# Nano_Leonardo_no_3V3.net
KiCad netlist of a schematic drawn in EAGLE
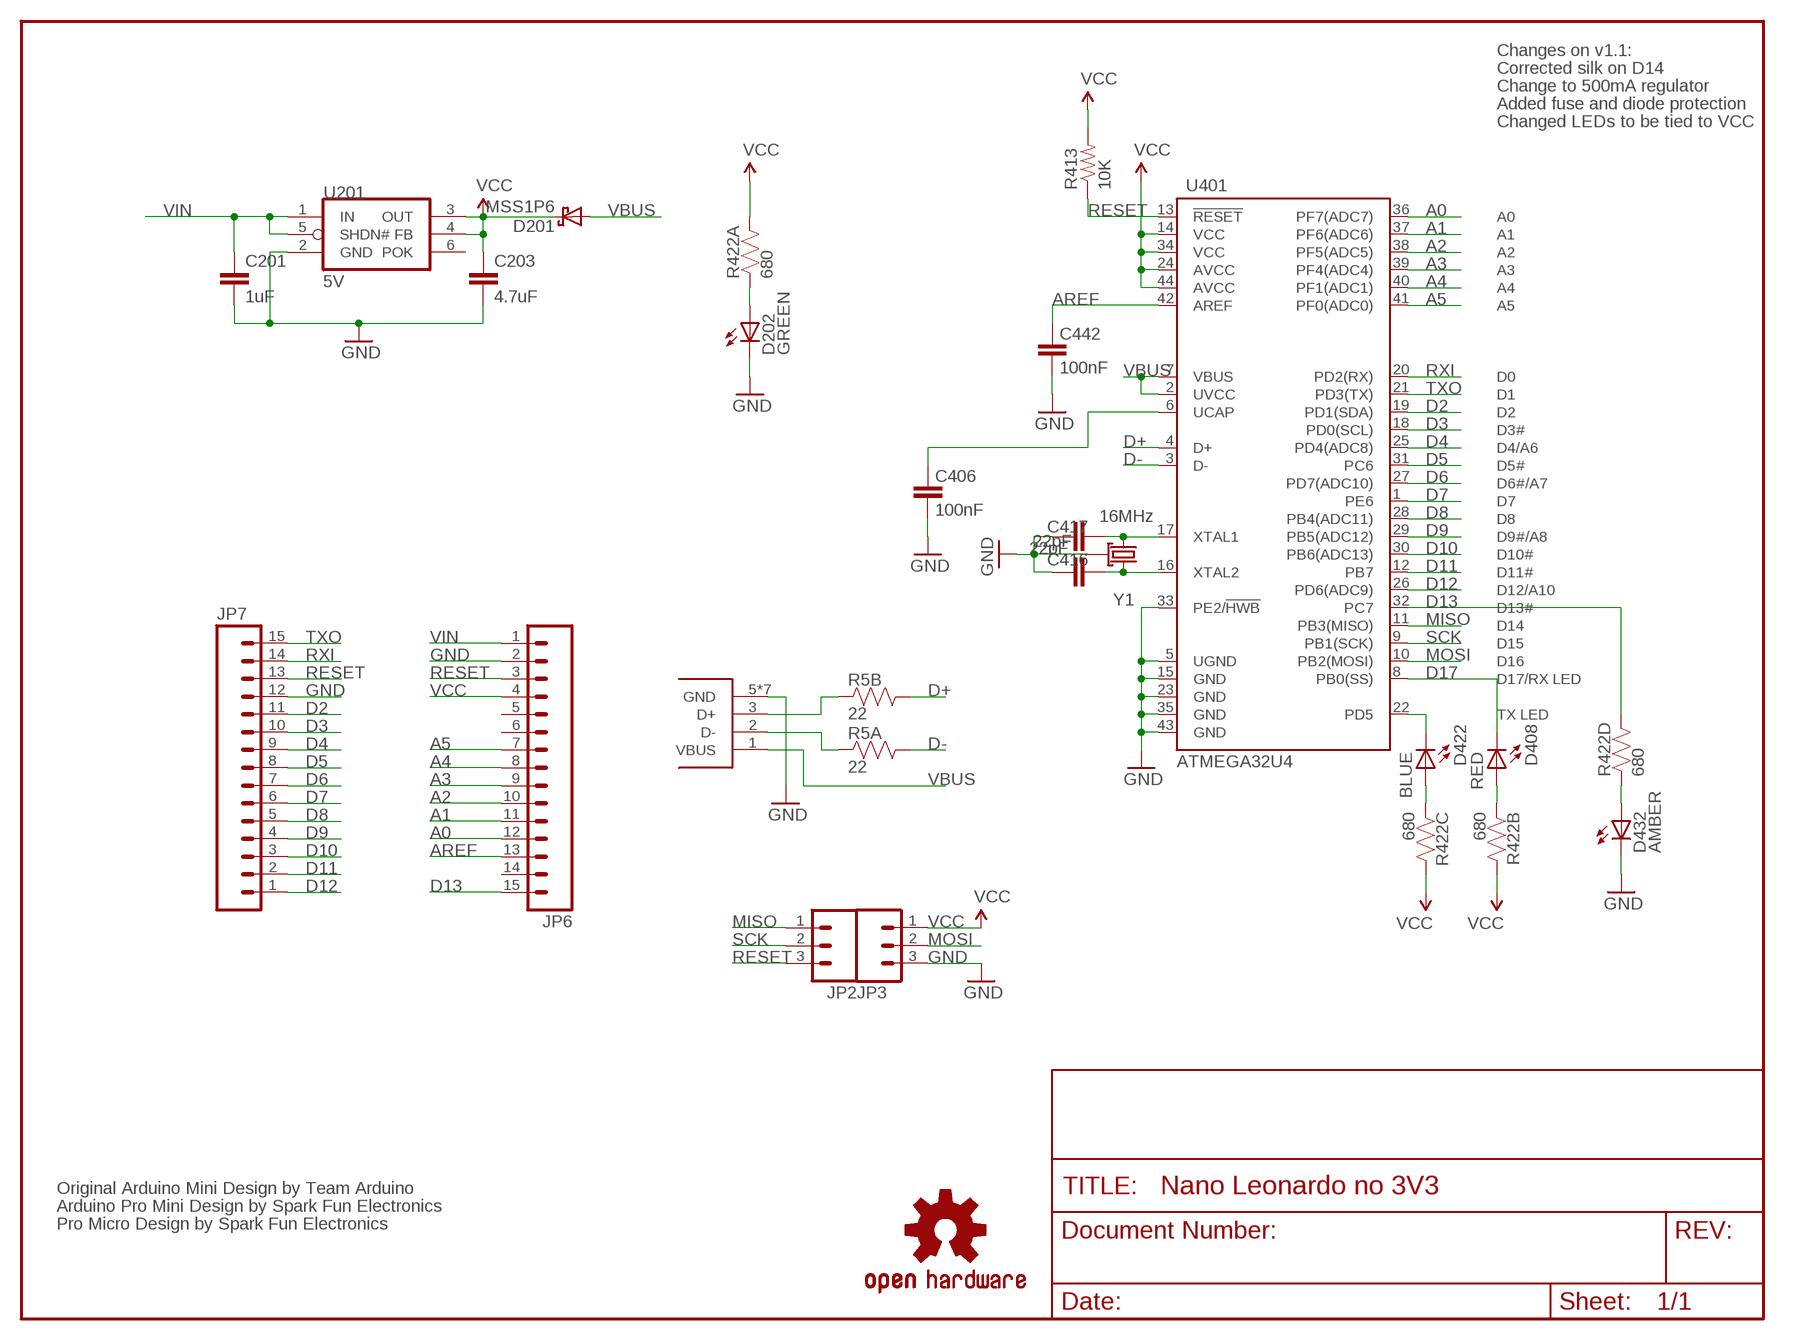
[diagram p0: schematic, sheet 1]

(export (version "E")
  (design (tool "Eeschema 10.0.6"))
  (components
    (comp (ref "C201")
      (value "1uF")
      (footprint "eagle-import:0402-CAP")
      (libsource (lib "eagle-import") (part "CAP0402-CAP"))
    )
    (comp (ref "C203")
      (value "4.7uF")
      (footprint "eagle-import:0402-CAP")
      (libsource (lib "eagle-import") (part "CAP0402-CAP"))
    )
    (comp (ref "C406")
      (value "100nF")
      (footprint "eagle-import:0402-CAP")
      (libsource (lib "eagle-import") (part "CAP0402-CAP"))
    )
    (comp (ref "C416")
      (value "22pF")
      (footprint "eagle-import:0402-CAP")
      (libsource (lib "eagle-import") (part "CAP0402-CAP"))
    )
    (comp (ref "C417")
      (value "22pF")
      (footprint "eagle-import:0402-CAP")
      (libsource (lib "eagle-import") (part "CAP0402-CAP"))
    )
    (comp (ref "C442")
      (value "100nF")
      (footprint "eagle-import:0402-CAP")
      (libsource (lib "eagle-import") (part "CAP0402-CAP"))
    )
    (comp (ref "D201")
      (value "MSS1P6")
      (footprint "eagle-import:MICROSMP")
      (libsource (lib "eagle-import") (part "MSS1P6"))
    )
    (comp (ref "D202")
      (value "GREEN")
      (footprint "eagle-import:LED-0603")
      (libsource (lib "eagle-import") (part "LED0603"))
    )
    (comp (ref "D408")
      (value "RED")
      (footprint "eagle-import:LED-0603")
      (libsource (lib "eagle-import") (part "LED0603"))
    )
    (comp (ref "D422")
      (value "BLUE")
      (footprint "eagle-import:LED-0603")
      (libsource (lib "eagle-import") (part "LED0603"))
    )
    (comp (ref "D432")
      (value "AMBER")
      (footprint "eagle-import:LED-0603")
      (libsource (lib "eagle-import") (part "LED0603"))
    )
    (comp (ref "JP2")
      (value "M031X03_NO_SILK")
      (footprint "eagle-import:1X03_NO_SILK")
      (libsource (lib "eagle-import") (part "M031X03_NO_SILK"))
    )
    (comp (ref "JP3")
      (value "M031X03_NO_SILK")
      (footprint "eagle-import:1X03_NO_SILK")
      (libsource (lib "eagle-import") (part "M031X03_NO_SILK"))
    )
    (comp (ref "JP6")
      (value "M15")
      (footprint "eagle-import:1X15")
      (libsource (lib "eagle-import") (part "M15"))
    )
    (comp (ref "JP7")
      (value "M15")
      (footprint "eagle-import:1X15")
      (libsource (lib "eagle-import") (part "M15"))
    )
    (comp (ref "R5")
      (value "22")
      (footprint "eagle-import:CRA02")
      (libsource (lib "eagle-import") (part "RP2EXB24V"))
    )
    (comp (ref "R413")
      (value "10K")
      (footprint "eagle-import:0402-RES")
      (libsource (lib "eagle-import") (part "RESISTOR0402-RES"))
    )
    (comp (ref "R422")
      (value "680")
      (footprint "eagle-import:CRA04")
      (libsource (lib "eagle-import") (part "RP404"))
    )
    (comp (ref "U$3")
      (value "OSHW-LOGOS")
      (footprint "eagle-import:OSHW-LOGO-S")
      (libsource (lib "eagle-import") (part "OSHW-LOGOS"))
    )
    (comp (ref "U201")
      (value "5V")
      (footprint "eagle-import:SOT-23-6")
      (libsource (lib "eagle-import") (part "MAX8881"))
    )
    (comp (ref "U401")
      (value "ATMEGA32U4")
      (footprint "eagle-import:QFN-44-NOPAD")
      (libsource (lib "eagle-import") (part "ATMEGA32U4QFN2"))
    )
    (comp (ref "X1")
      (value "USB_MICROB_JSTGCT")
      (footprint "eagle-import:USB_MICROB_3075")
      (libsource (lib "eagle-import") (part "USB_MICROB_JSTGCT"))
    )
    (comp (ref "Y1")
      (value "16MHz")
      (footprint "eagle-import:CRYSTAL_SMD_2MM_2_5MM")
      (libsource (lib "eagle-import") (part "CX2520"))
    )
  )
  (nets
    (net (code "1") (name "/A0") (class "Default")
      (node (ref "JP6") (pin "12") (pinfunction "12_12") (pintype "passive"))
      (node (ref "U401") (pin "36") (pinfunction "PF7(ADC7)_36") (pintype "bidirectional"))
    )
    (net (code "2") (name "/A1") (class "Default")
      (node (ref "JP6") (pin "11") (pinfunction "11_11") (pintype "passive"))
      (node (ref "U401") (pin "37") (pinfunction "PF6(ADC6)_37") (pintype "bidirectional"))
    )
    (net (code "3") (name "/A2") (class "Default")
      (node (ref "JP6") (pin "10") (pinfunction "10_10") (pintype "passive"))
      (node (ref "U401") (pin "38") (pinfunction "PF5(ADC5)_38") (pintype "bidirectional"))
    )
    (net (code "4") (name "/A3") (class "Default")
      (node (ref "JP6") (pin "9") (pinfunction "9_9") (pintype "passive"))
      (node (ref "U401") (pin "39") (pinfunction "PF4(ADC4)_39") (pintype "bidirectional"))
    )
    (net (code "5") (name "/A4") (class "Default")
      (node (ref "JP6") (pin "8") (pinfunction "8_8") (pintype "passive"))
      (node (ref "U401") (pin "40") (pinfunction "PF1(ADC1)_40") (pintype "bidirectional"))
    )
    (net (code "6") (name "/A5") (class "Default")
      (node (ref "JP6") (pin "7") (pinfunction "7_7") (pintype "passive"))
      (node (ref "U401") (pin "41") (pinfunction "PF0(ADC0)_41") (pintype "bidirectional"))
    )
    (net (code "7") (name "/AREF") (class "Default")
      (node (ref "C442") (pin "2") (pinfunction "2_2") (pintype "passive"))
      (node (ref "JP6") (pin "13") (pinfunction "13_13") (pintype "passive"))
      (node (ref "U401") (pin "42") (pinfunction "AREF_42") (pintype "bidirectional"))
    )
    (net (code "8") (name "/D+") (class "Default")
      (node (ref "R5") (pin "3") (pinfunction "2_3") (pintype "passive"))
      (node (ref "U401") (pin "4") (pinfunction "D+_4") (pintype "bidirectional"))
    )
    (net (code "9") (name "/D-") (class "Default")
      (node (ref "R5") (pin "4") (pinfunction "2_4") (pintype "passive"))
      (node (ref "U401") (pin "3") (pinfunction "D-_3") (pintype "bidirectional"))
    )
    (net (code "10") (name "/D2") (class "Default")
      (node (ref "JP7") (pin "11") (pinfunction "11_11") (pintype "passive"))
      (node (ref "U401") (pin "19") (pinfunction "PD1(SDA)_19") (pintype "bidirectional"))
    )
    (net (code "11") (name "/D3") (class "Default")
      (node (ref "JP7") (pin "10") (pinfunction "10_10") (pintype "passive"))
      (node (ref "U401") (pin "18") (pinfunction "PD0(SCL)_18") (pintype "bidirectional"))
    )
    (net (code "12") (name "/D4") (class "Default")
      (node (ref "JP7") (pin "9") (pinfunction "9_9") (pintype "passive"))
      (node (ref "U401") (pin "25") (pinfunction "PD4(ADC8)_25") (pintype "bidirectional"))
    )
    (net (code "13") (name "/D5") (class "Default")
      (node (ref "JP7") (pin "8") (pinfunction "8_8") (pintype "passive"))
      (node (ref "U401") (pin "31") (pinfunction "PC6_31") (pintype "bidirectional"))
    )
    (net (code "14") (name "/D6") (class "Default")
      (node (ref "JP7") (pin "7") (pinfunction "7_7") (pintype "passive"))
      (node (ref "U401") (pin "27") (pinfunction "PD7(ADC10)_27") (pintype "bidirectional"))
    )
    (net (code "15") (name "/D7") (class "Default")
      (node (ref "JP7") (pin "6") (pinfunction "6_6") (pintype "passive"))
      (node (ref "U401") (pin "1") (pinfunction "PE6_1") (pintype "bidirectional"))
    )
    (net (code "16") (name "/D8") (class "Default")
      (node (ref "JP7") (pin "5") (pinfunction "5_5") (pintype "passive"))
      (node (ref "U401") (pin "28") (pinfunction "PB4(ADC11)_28") (pintype "bidirectional"))
    )
    (net (code "17") (name "/D9") (class "Default")
      (node (ref "JP7") (pin "4") (pinfunction "4_4") (pintype "passive"))
      (node (ref "U401") (pin "29") (pinfunction "PB5(ADC12)_29") (pintype "bidirectional"))
    )
    (net (code "18") (name "/D10") (class "Default")
      (node (ref "JP7") (pin "3") (pinfunction "3_3") (pintype "passive"))
      (node (ref "U401") (pin "30") (pinfunction "PB6(ADC13)_30") (pintype "bidirectional"))
    )
    (net (code "19") (name "/D11") (class "Default")
      (node (ref "JP7") (pin "2") (pinfunction "2_2") (pintype "passive"))
      (node (ref "U401") (pin "12") (pinfunction "PB7_12") (pintype "bidirectional"))
    )
    (net (code "20") (name "/D12") (class "Default")
      (node (ref "JP7") (pin "1") (pinfunction "1_1") (pintype "passive"))
      (node (ref "U401") (pin "26") (pinfunction "PD6(ADC9)_26") (pintype "bidirectional"))
    )
    (net (code "21") (name "/D13") (class "Default")
      (node (ref "JP6") (pin "15") (pinfunction "15_15") (pintype "passive"))
      (node (ref "R422") (pin "5") (pinfunction "2_5") (pintype "passive"))
      (node (ref "U401") (pin "32") (pinfunction "PC7_32") (pintype "bidirectional"))
    )
    (net (code "22") (name "/D17") (class "Default")
      (node (ref "D408") (pin "C") (pinfunction "C_C") (pintype "passive"))
      (node (ref "U401") (pin "8") (pinfunction "PB0(SS)_8") (pintype "bidirectional"))
    )
    (net (code "23") (name "/MISO") (class "Default")
      (node (ref "JP2") (pin "1") (pinfunction "1_1") (pintype "passive"))
      (node (ref "U401") (pin "11") (pinfunction "PB3(MISO)_11") (pintype "bidirectional"))
    )
    (net (code "24") (name "/MOSI") (class "Default")
      (node (ref "JP3") (pin "2") (pinfunction "2_2") (pintype "passive"))
      (node (ref "U401") (pin "10") (pinfunction "PB2(MOSI)_10") (pintype "bidirectional"))
    )
    (net (code "25") (name "/RESET") (class "Default")
      (node (ref "JP2") (pin "3") (pinfunction "3_3") (pintype "passive"))
      (node (ref "JP6") (pin "3") (pinfunction "3_3") (pintype "passive"))
      (node (ref "JP7") (pin "13") (pinfunction "13_13") (pintype "passive"))
      (node (ref "R413") (pin "1") (pinfunction "1_1") (pintype "passive"))
      (node (ref "U401") (pin "13") (pinfunction "~{RESET}_13") (pintype "bidirectional"))
    )
    (net (code "26") (name "/RXI") (class "Default")
      (node (ref "JP7") (pin "14") (pinfunction "14_14") (pintype "passive"))
      (node (ref "U401") (pin "20") (pinfunction "PD2(RX)_20") (pintype "bidirectional"))
    )
    (net (code "27") (name "/SCK") (class "Default")
      (node (ref "JP2") (pin "2") (pinfunction "2_2") (pintype "passive"))
      (node (ref "U401") (pin "9") (pinfunction "PB1(SCK)_9") (pintype "bidirectional"))
    )
    (net (code "28") (name "/TXO") (class "Default")
      (node (ref "JP7") (pin "15") (pinfunction "15_15") (pintype "passive"))
      (node (ref "U401") (pin "21") (pinfunction "PD3(TX)_21") (pintype "bidirectional"))
    )
    (net (code "29") (name "/VBUS") (class "Default")
      (node (ref "D201") (pin "A") (pinfunction "A_A") (pintype "passive"))
      (node (ref "U401") (pin "2") (pinfunction "UVCC_2") (pintype "bidirectional"))
      (node (ref "U401") (pin "7") (pinfunction "VBUS_7") (pintype "bidirectional"))
      (node (ref "X1") (pin "1") (pinfunction "VBUS_1") (pintype "bidirectional"))
    )
    (net (code "30") (name "/VIN") (class "Default")
      (node (ref "C201") (pin "1") (pinfunction "1_1") (pintype "passive"))
      (node (ref "JP6") (pin "1") (pinfunction "1_1") (pintype "passive"))
      (node (ref "U201") (pin "1") (pinfunction "IN_1") (pintype "bidirectional"))
      (node (ref "U201") (pin "5") (pinfunction "SHDN#_5") (pintype "bidirectional"))
    )
    (net (code "31") (name "GND") (class "Default")
      (node (ref "C201") (pin "2") (pinfunction "2_2") (pintype "passive"))
      (node (ref "C203") (pin "2") (pinfunction "2_2") (pintype "passive"))
      (node (ref "C406") (pin "1") (pinfunction "1_1") (pintype "passive"))
      (node (ref "C416") (pin "2") (pinfunction "2_2") (pintype "passive"))
      (node (ref "C417") (pin "2") (pinfunction "2_2") (pintype "passive"))
      (node (ref "C442") (pin "1") (pinfunction "1_1") (pintype "passive"))
      (node (ref "D202") (pin "C") (pinfunction "C_C") (pintype "passive"))
      (node (ref "D432") (pin "C") (pinfunction "C_C") (pintype "passive"))
      (node (ref "JP3") (pin "3") (pinfunction "3_3") (pintype "passive"))
      (node (ref "JP6") (pin "2") (pinfunction "2_2") (pintype "passive"))
      (node (ref "JP7") (pin "12") (pinfunction "12_12") (pintype "passive"))
      (node (ref "U201") (pin "2") (pinfunction "GND_2") (pintype "bidirectional"))
      (node (ref "U401") (pin "15") (pinfunction "GND_15") (pintype "bidirectional"))
      (node (ref "U401") (pin "23") (pinfunction "GND_23") (pintype "bidirectional"))
      (node (ref "U401") (pin "33") (pinfunction "PE2/~{HWB}_33") (pintype "bidirectional"))
      (node (ref "U401") (pin "35") (pinfunction "GND_35") (pintype "bidirectional"))
      (node (ref "U401") (pin "43") (pinfunction "GND_43") (pintype "bidirectional"))
      (node (ref "U401") (pin "5") (pinfunction "UGND_5") (pintype "bidirectional"))
      (node (ref "X1") (pin "5") (pinfunction "GND_5") (pintype "bidirectional"))
      (node (ref "X1") (pin "P$1") (pinfunction "GND_P$1") (pintype "bidirectional"))
      (node (ref "X1") (pin "P$10") (pinfunction "GND_P$10") (pintype "bidirectional"))
      (node (ref "X1") (pin "P$2") (pinfunction "GND_P$2") (pintype "bidirectional"))
      (node (ref "X1") (pin "P$3") (pinfunction "GND_P$3") (pintype "bidirectional"))
      (node (ref "X1") (pin "P$4") (pinfunction "GND_P$4") (pintype "bidirectional"))
      (node (ref "X1") (pin "P$8") (pinfunction "GND_P$8") (pintype "bidirectional"))
      (node (ref "Y1") (pin "2") (pinfunction "GND_2") (pintype "passive"))
      (node (ref "Y1") (pin "4") (pinfunction "GND_4") (pintype "passive"))
    )
    (net (code "32") (name "Net-(D202-PadA)") (class "Default")
      (node (ref "D202") (pin "A") (pinfunction "A_A") (pintype "passive"))
      (node (ref "R422") (pin "1") (pinfunction "1_1") (pintype "passive"))
    )
    (net (code "33") (name "Net-(R5B-1)") (class "Default")
      (node (ref "R5") (pin "2") (pinfunction "1_2") (pintype "passive"))
      (node (ref "X1") (pin "3") (pinfunction "D+_3") (pintype "bidirectional"))
    )
    (net (code "34") (name "Net-(R422B-1)") (class "Default")
      (node (ref "D408") (pin "A") (pinfunction "A_A") (pintype "passive"))
      (node (ref "R422") (pin "2") (pinfunction "1_2") (pintype "passive"))
    )
    (net (code "35") (name "Net-(R422C-1)") (class "Default")
      (node (ref "D422") (pin "A") (pinfunction "A_A") (pintype "passive"))
      (node (ref "R422") (pin "3") (pinfunction "1_3") (pintype "passive"))
    )
    (net (code "36") (name "Net-(R422D-1)") (class "Default")
      (node (ref "D432") (pin "A") (pinfunction "A_A") (pintype "passive"))
      (node (ref "R422") (pin "4") (pinfunction "1_4") (pintype "passive"))
    )
    (net (code "37") (name "Net-(U401-PD5)") (class "Default")
      (node (ref "D422") (pin "C") (pinfunction "C_C") (pintype "passive"))
      (node (ref "U401") (pin "22") (pinfunction "PD5_22") (pintype "bidirectional"))
    )
    (net (code "38") (name "Net-(U401-UCAP)") (class "Default")
      (node (ref "C406") (pin "2") (pinfunction "2_2") (pintype "passive"))
      (node (ref "U401") (pin "6") (pinfunction "UCAP_6") (pintype "bidirectional"))
    )
    (net (code "39") (name "Net-(U401-XTAL1)") (class "Default")
      (node (ref "C417") (pin "1") (pinfunction "1_1") (pintype "passive"))
      (node (ref "U401") (pin "17") (pinfunction "XTAL1_17") (pintype "bidirectional"))
      (node (ref "Y1") (pin "1") (pinfunction "1_1") (pintype "passive"))
    )
    (net (code "40") (name "Net-(U401-XTAL2)") (class "Default")
      (node (ref "C416") (pin "1") (pinfunction "1_1") (pintype "passive"))
      (node (ref "U401") (pin "16") (pinfunction "XTAL2_16") (pintype "bidirectional"))
      (node (ref "Y1") (pin "3") (pinfunction "2_3") (pintype "passive"))
    )
    (net (code "41") (name "Net-(X1-D-)") (class "Default")
      (node (ref "R5") (pin "1") (pinfunction "1_1") (pintype "passive"))
      (node (ref "X1") (pin "2") (pinfunction "D-_2") (pintype "bidirectional"))
    )
    (net (code "42") (name "VCC") (class "Default")
      (node (ref "C203") (pin "1") (pinfunction "1_1") (pintype "passive"))
      (node (ref "D201") (pin "K") (pinfunction "K_K") (pintype "passive"))
      (node (ref "JP3") (pin "1") (pinfunction "1_1") (pintype "passive"))
      (node (ref "JP6") (pin "4") (pinfunction "4_4") (pintype "passive"))
      (node (ref "R413") (pin "2") (pinfunction "2_2") (pintype "passive"))
      (node (ref "R422") (pin "6") (pinfunction "2_6") (pintype "passive"))
      (node (ref "R422") (pin "7") (pinfunction "2_7") (pintype "passive"))
      (node (ref "R422") (pin "8") (pinfunction "2_8") (pintype "passive"))
      (node (ref "U201") (pin "3") (pinfunction "OUT_3") (pintype "bidirectional"))
      (node (ref "U201") (pin "4") (pinfunction "FB_4") (pintype "bidirectional"))
      (node (ref "U401") (pin "14") (pinfunction "VCC_14") (pintype "bidirectional"))
      (node (ref "U401") (pin "24") (pinfunction "AVCC_24") (pintype "bidirectional"))
      (node (ref "U401") (pin "34") (pinfunction "VCC_34") (pintype "bidirectional"))
      (node (ref "U401") (pin "44") (pinfunction "AVCC_44") (pintype "bidirectional"))
    )
    (net (code "43") (name "unconnected-(JP6-Pad5)") (class "Default")
      (node (ref "JP6") (pin "5") (pinfunction "5_5") (pintype "passive"))
    )
    (net (code "44") (name "unconnected-(JP6-Pad6)") (class "Default")
      (node (ref "JP6") (pin "6") (pinfunction "6_6") (pintype "passive"))
    )
    (net (code "45") (name "unconnected-(JP6-Pad14)") (class "Default")
      (node (ref "JP6") (pin "14") (pinfunction "14_14") (pintype "passive"))
    )
    (net (code "46") (name "unconnected-(U201-POK-Pad6)") (class "Default")
      (node (ref "U201") (pin "6") (pinfunction "POK_6") (pintype "bidirectional"))
    )
  )
)
